# comparador.net
KiCad netlist of a schematic drawn in EAGLE
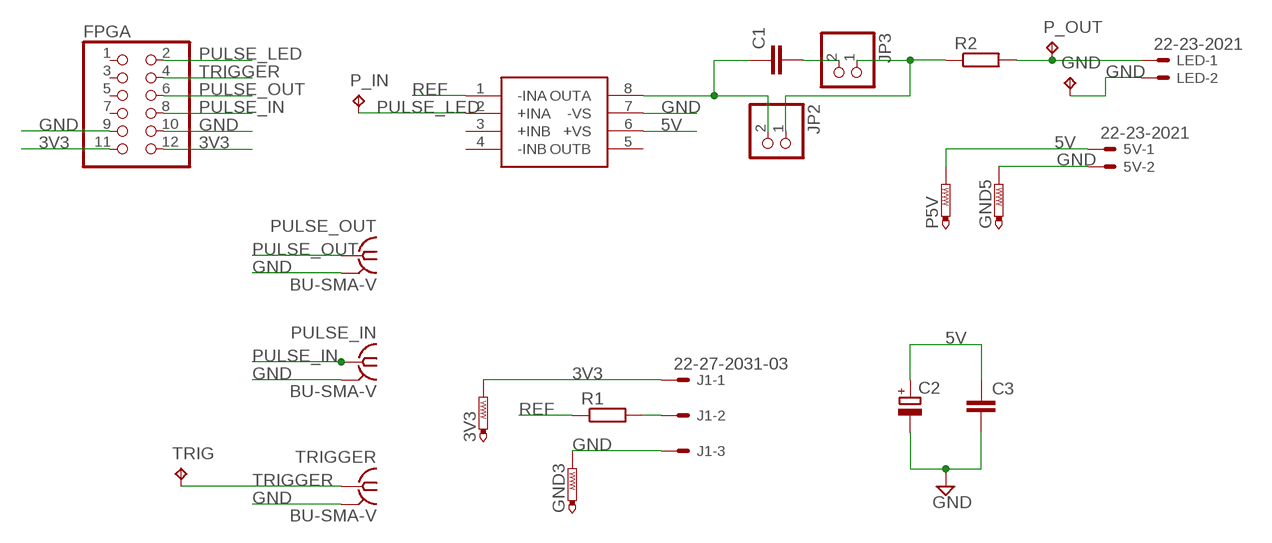
[diagram p0: schematic, sheet 1]

(export (version "E")
  (design (tool "Eeschema 10.0.6"))
  (components
    (comp (ref "3V3")
      (value "PTR1TP20SQ")
      (footprint "eagle-import:TP20SQ")
      (libsource (lib "eagle-import") (part "PTR1TP20SQ"))
    )
    (comp (ref "5V")
      (value "22-23-2021")
      (footprint "eagle-import:22-23-2021")
      (fields (field (name "MF") "MOLEX"))
      (libsource (lib "eagle-import") (part "22-23-2021"))
    )
    (comp (ref "C1")
      (value "C-EU025-024X044")
      (footprint "eagle-import:C025-024X044")
      (libsource (lib "eagle-import") (part "C-EU025-024X044"))
    )
    (comp (ref "C2")
      (value "CPOL-EUE5-8.5")
      (footprint "eagle-import:E5-8,5")
      (libsource (lib "eagle-import") (part "CPOL-EUE5-8.5"))
    )
    (comp (ref "C3")
      (value "C-EU025-024X044")
      (footprint "eagle-import:C025-024X044")
      (libsource (lib "eagle-import") (part "C-EU025-024X044"))
    )
    (comp (ref "FPGA")
      (value "PINHD-2X6")
      (footprint "eagle-import:2X06")
      (libsource (lib "eagle-import") (part "PINHD-2X6"))
    )
    (comp (ref "GND")
      (value "TPPAD1-20")
      (footprint "eagle-import:P1-20")
      (libsource (lib "eagle-import") (part "TPPAD1-20"))
    )
    (comp (ref "GND3")
      (value "PTR1TP20SQ")
      (footprint "eagle-import:TP20SQ")
      (libsource (lib "eagle-import") (part "PTR1TP20SQ"))
    )
    (comp (ref "GND5")
      (value "PTR1TP20SQ")
      (footprint "eagle-import:TP20SQ")
      (libsource (lib "eagle-import") (part "PTR1TP20SQ"))
    )
    (comp (ref "J1")
      (value "22-27-2031-03")
      (footprint "eagle-import:6410-03")
      (libsource (lib "eagle-import") (part "22-?-0327-2031"))
    )
    (comp (ref "JP2")
      (value "PINHD-1X2")
      (footprint "eagle-import:1X02")
      (libsource (lib "eagle-import") (part "PINHD-1X2"))
    )
    (comp (ref "JP3")
      (value "PINHD-1X2")
      (footprint "eagle-import:1X02")
      (libsource (lib "eagle-import") (part "PINHD-1X2"))
    )
    (comp (ref "LED")
      (value "22-23-2021")
      (footprint "eagle-import:22-23-2021")
      (fields (field (name "MF") "MOLEX"))
      (libsource (lib "eagle-import") (part "22-23-2021"))
    )
    (comp (ref "OPA")
      (value "OPA2695")
      (footprint "eagle-import:SOIC127P600X175-8N")
      (libsource (lib "eagle-import") (part "OPA2695"))
    )
    (comp (ref "P5V")
      (value "PTR1TP20SQ")
      (footprint "eagle-import:TP20SQ")
      (libsource (lib "eagle-import") (part "PTR1TP20SQ"))
    )
    (comp (ref "PULSE_IN")
      (value "BU-SMA-V")
      (footprint "eagle-import:BU-SMA-V")
      (libsource (lib "eagle-import") (part "BU-SMA-V"))
    )
    (comp (ref "PULSE_OUT")
      (value "BU-SMA-V")
      (footprint "eagle-import:BU-SMA-V")
      (libsource (lib "eagle-import") (part "BU-SMA-V"))
    )
    (comp (ref "P_IN")
      (value "TPPAD1-20")
      (footprint "eagle-import:P1-20")
      (libsource (lib "eagle-import") (part "TPPAD1-20"))
    )
    (comp (ref "P_OUT")
      (value "TPPAD1-20")
      (footprint "eagle-import:P1-20")
      (libsource (lib "eagle-import") (part "TPPAD1-20"))
    )
    (comp (ref "R1")
      (value "R-EU_0207/7")
      (footprint "eagle-import:0207_7")
      (libsource (lib "eagle-import") (part "R-EU_0207/7"))
    )
    (comp (ref "R2")
      (value "R-EU_0207/7")
      (footprint "eagle-import:0207_7")
      (libsource (lib "eagle-import") (part "R-EU_0207/7"))
    )
    (comp (ref "TRIG")
      (value "TPPAD1-20")
      (footprint "eagle-import:P1-20")
      (libsource (lib "eagle-import") (part "TPPAD1-20"))
    )
    (comp (ref "TRIGGER")
      (value "BU-SMA-V")
      (footprint "eagle-import:BU-SMA-V")
      (libsource (lib "eagle-import") (part "BU-SMA-V"))
    )
  )
  (nets
    (net (code "1") (name "/3V3") (class "Default")
      (node (ref "3V3") (pin "TP") (pinfunction "TP_TP") (pintype "input"))
      (node (ref "FPGA") (pin "11") (pinfunction "11_11") (pintype "passive"))
      (node (ref "FPGA") (pin "12") (pinfunction "12_12") (pintype "passive"))
      (node (ref "J1") (pin "1") (pinfunction "S_1") (pintype "passive"))
    )
    (net (code "2") (name "/5V") (class "Default")
      (node (ref "5V") (pin "1") (pinfunction "S_1") (pintype "passive"))
      (node (ref "C2") (pin "+") (pinfunction "+_+") (pintype "passive"))
      (node (ref "C3") (pin "1") (pinfunction "1_1") (pintype "passive"))
      (node (ref "OPA") (pin "6") (pinfunction "+VS_6") (pintype "passive"))
      (node (ref "P5V") (pin "TP") (pinfunction "TP_TP") (pintype "input"))
    )
    (net (code "3") (name "/PULSE_IN") (class "Default")
      (node (ref "FPGA") (pin "8") (pinfunction "8_8") (pintype "passive"))
      (node (ref "PULSE_IN") (pin "1") (pinfunction "1_1") (pintype "passive"))
    )
    (net (code "4") (name "/PULSE_LED") (class "Default")
      (node (ref "FPGA") (pin "2") (pinfunction "2_2") (pintype "passive"))
      (node (ref "OPA") (pin "2") (pinfunction "+INA_2") (pintype "passive"))
      (node (ref "P_IN") (pin "TP") (pinfunction "TP_TP") (pintype "input"))
    )
    (net (code "5") (name "/PULSE_OUT") (class "Default")
      (node (ref "FPGA") (pin "6") (pinfunction "6_6") (pintype "passive"))
      (node (ref "PULSE_OUT") (pin "1") (pinfunction "1_1") (pintype "passive"))
    )
    (net (code "6") (name "/REF") (class "Default")
      (node (ref "OPA") (pin "1") (pinfunction "-INA_1") (pintype "passive"))
      (node (ref "R1") (pin "1") (pinfunction "1_1") (pintype "passive"))
    )
    (net (code "7") (name "/TRIGGER") (class "Default")
      (node (ref "FPGA") (pin "4") (pinfunction "4_4") (pintype "passive"))
      (node (ref "TRIG") (pin "TP") (pinfunction "TP_TP") (pintype "input"))
      (node (ref "TRIGGER") (pin "1") (pinfunction "1_1") (pintype "passive"))
    )
    (net (code "8") (name "GND") (class "Default")
      (node (ref "5V") (pin "2") (pinfunction "S_2") (pintype "passive"))
      (node (ref "C2") (pin "-") (pinfunction "-_-") (pintype "passive"))
      (node (ref "C3") (pin "2") (pinfunction "2_2") (pintype "passive"))
      (node (ref "FPGA") (pin "10") (pinfunction "10_10") (pintype "passive"))
      (node (ref "FPGA") (pin "9") (pinfunction "9_9") (pintype "passive"))
      (node (ref "GND") (pin "TP") (pinfunction "TP_TP") (pintype "input"))
      (node (ref "GND3") (pin "TP") (pinfunction "TP_TP") (pintype "input"))
      (node (ref "GND5") (pin "TP") (pinfunction "TP_TP") (pintype "input"))
      (node (ref "J1") (pin "3") (pinfunction "S_3") (pintype "passive"))
      (node (ref "LED") (pin "2") (pinfunction "S_2") (pintype "passive"))
      (node (ref "OPA") (pin "7") (pinfunction "-VS_7") (pintype "passive"))
      (node (ref "PULSE_IN") (pin "2") (pinfunction "2_2") (pintype "passive"))
      (node (ref "PULSE_IN") (pin "3") (pinfunction "2_3") (pintype "passive"))
      (node (ref "PULSE_IN") (pin "4") (pinfunction "2_4") (pintype "passive"))
      (node (ref "PULSE_IN") (pin "5") (pinfunction "2_5") (pintype "passive"))
      (node (ref "PULSE_OUT") (pin "2") (pinfunction "2_2") (pintype "passive"))
      (node (ref "PULSE_OUT") (pin "3") (pinfunction "2_3") (pintype "passive"))
      (node (ref "PULSE_OUT") (pin "4") (pinfunction "2_4") (pintype "passive"))
      (node (ref "PULSE_OUT") (pin "5") (pinfunction "2_5") (pintype "passive"))
      (node (ref "TRIGGER") (pin "2") (pinfunction "2_2") (pintype "passive"))
      (node (ref "TRIGGER") (pin "3") (pinfunction "2_3") (pintype "passive"))
      (node (ref "TRIGGER") (pin "4") (pinfunction "2_4") (pintype "passive"))
      (node (ref "TRIGGER") (pin "5") (pinfunction "2_5") (pintype "passive"))
    )
    (net (code "9") (name "Net-(C1-Pad2)") (class "Default")
      (node (ref "C1") (pin "2") (pinfunction "2_2") (pintype "passive"))
      (node (ref "JP3") (pin "2") (pinfunction "2_2") (pintype "passive"))
    )
    (net (code "10") (name "Net-(J1B-S)") (class "Default")
      (node (ref "J1") (pin "2") (pinfunction "S_2") (pintype "passive"))
      (node (ref "R1") (pin "2") (pinfunction "2_2") (pintype "passive"))
    )
    (net (code "11") (name "Net-(JP2-Pad1)") (class "Default")
      (node (ref "JP2") (pin "1") (pinfunction "1_1") (pintype "passive"))
      (node (ref "JP3") (pin "1") (pinfunction "1_1") (pintype "passive"))
      (node (ref "R2") (pin "1") (pinfunction "1_1") (pintype "passive"))
    )
    (net (code "12") (name "Net-(LEDA-S)") (class "Default")
      (node (ref "LED") (pin "1") (pinfunction "S_1") (pintype "passive"))
      (node (ref "P_OUT") (pin "TP") (pinfunction "TP_TP") (pintype "input"))
      (node (ref "R2") (pin "2") (pinfunction "2_2") (pintype "passive"))
    )
    (net (code "13") (name "Net-(OPA-OUTA)") (class "Default")
      (node (ref "C1") (pin "1") (pinfunction "1_1") (pintype "passive"))
      (node (ref "JP2") (pin "2") (pinfunction "2_2") (pintype "passive"))
      (node (ref "OPA") (pin "8") (pinfunction "OUTA_8") (pintype "passive"))
    )
    (net (code "14") (name "unconnected-(FPGA-Pad1)") (class "Default")
      (node (ref "FPGA") (pin "1") (pinfunction "1_1") (pintype "passive"))
    )
    (net (code "15") (name "unconnected-(FPGA-Pad3)") (class "Default")
      (node (ref "FPGA") (pin "3") (pinfunction "3_3") (pintype "passive"))
    )
    (net (code "16") (name "unconnected-(FPGA-Pad5)") (class "Default")
      (node (ref "FPGA") (pin "5") (pinfunction "5_5") (pintype "passive"))
    )
    (net (code "17") (name "unconnected-(FPGA-Pad7)") (class "Default")
      (node (ref "FPGA") (pin "7") (pinfunction "7_7") (pintype "passive"))
    )
    (net (code "18") (name "unconnected-(OPA-+INB-Pad3)") (class "Default")
      (node (ref "OPA") (pin "3") (pinfunction "+INB_3") (pintype "passive"))
    )
    (net (code "19") (name "unconnected-(OPA--INB-Pad4)") (class "Default")
      (node (ref "OPA") (pin "4") (pinfunction "-INB_4") (pintype "passive"))
    )
    (net (code "20") (name "unconnected-(OPA-OUTB-Pad5)") (class "Default")
      (node (ref "OPA") (pin "5") (pinfunction "OUTB_5") (pintype "passive"))
    )
  )
)
